# Sheild_Generator_-_Main_unit.net
KiCad netlist of a schematic drawn in EAGLE
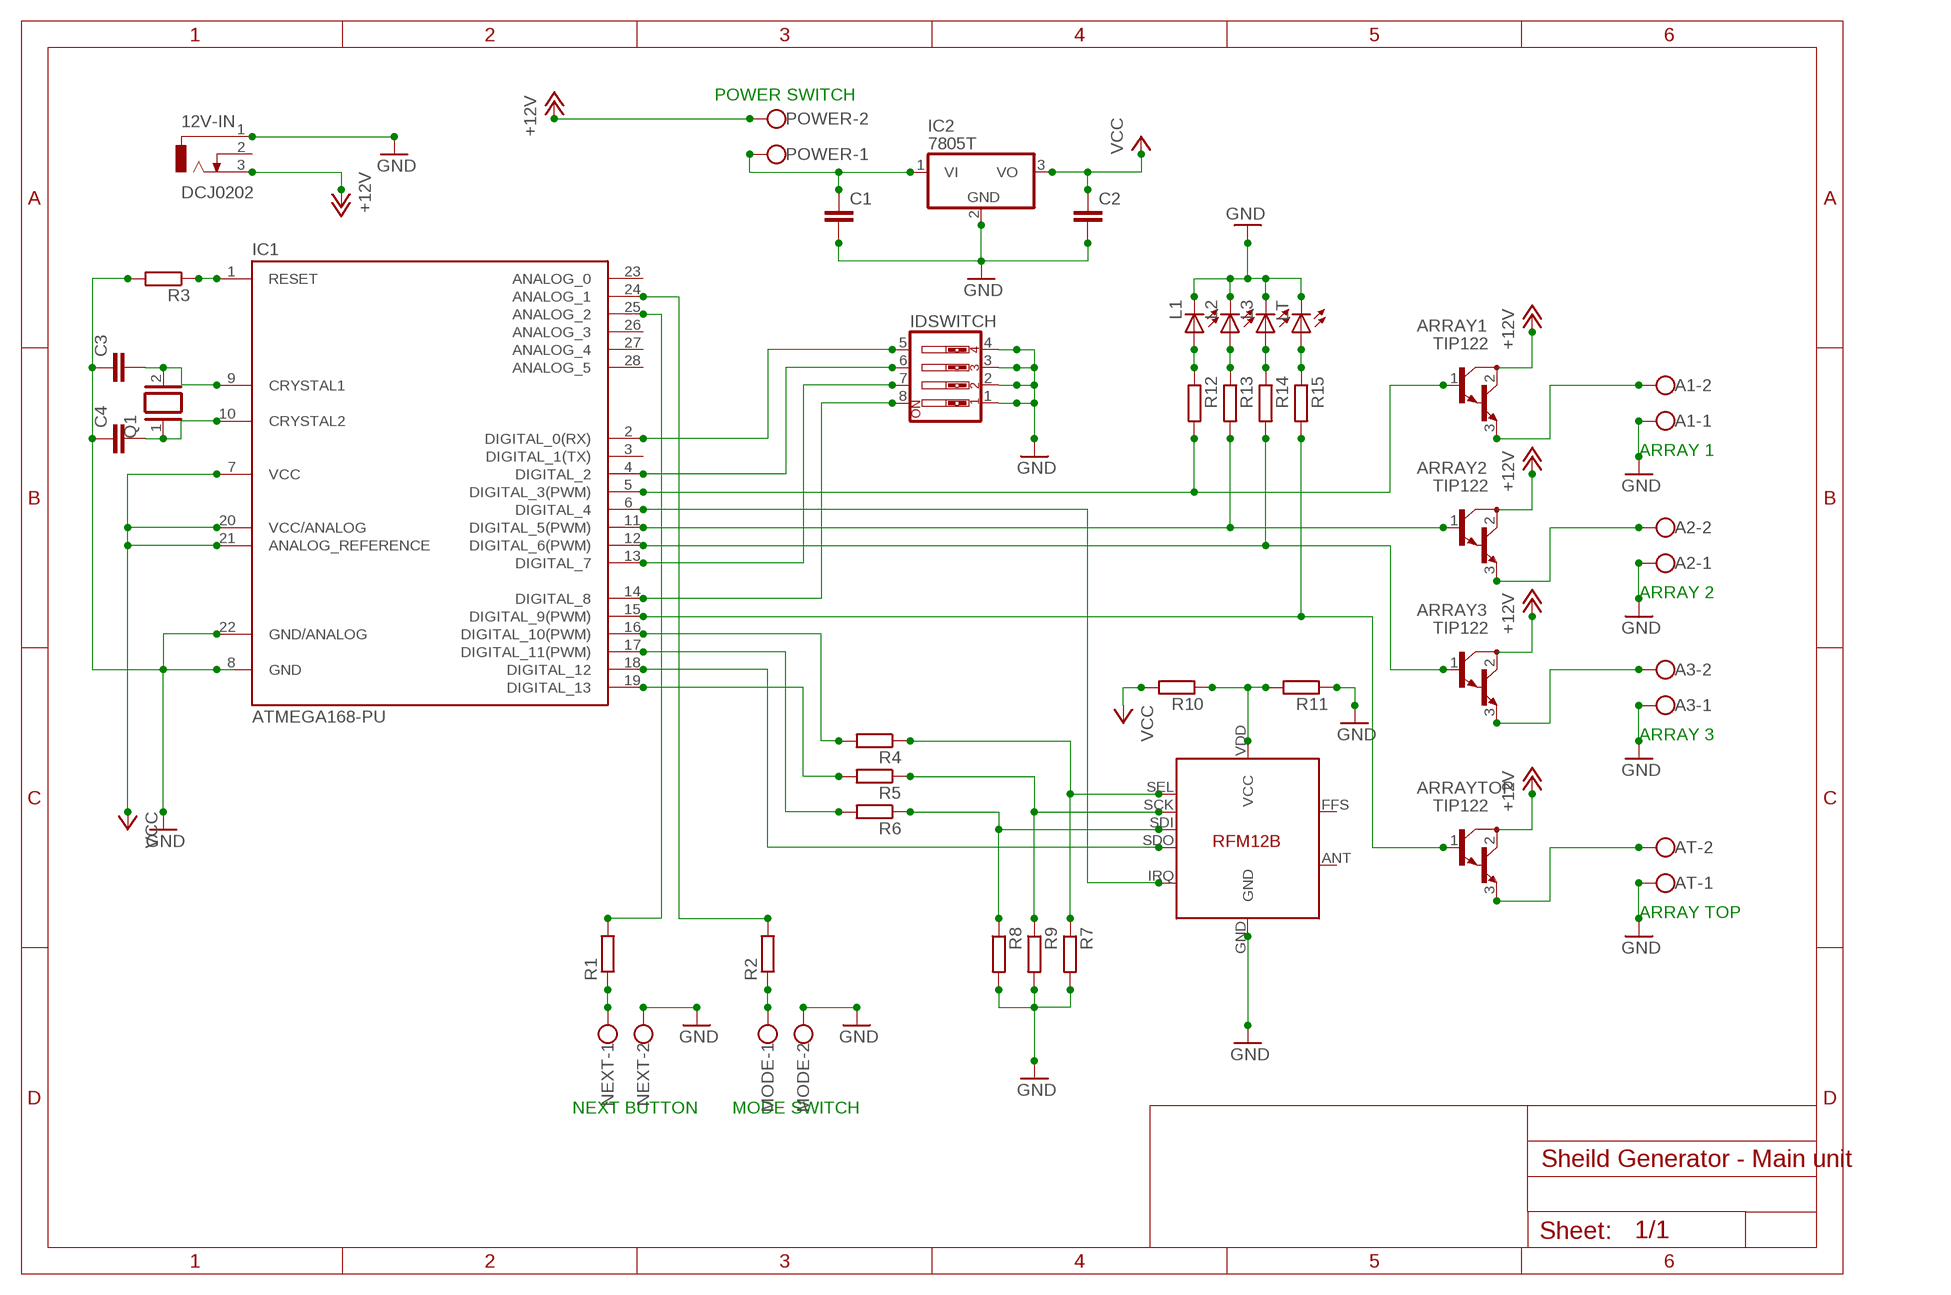
[diagram p0: schematic, sheet 1]

(export (version "E")
  (design (tool "Eeschema 10.0.6"))
  (components
    (comp (ref "12V-IN")
      (value "DCJ0202")
      (footprint "eagle-import:DCJ0202")
      (libsource (lib "eagle-import") (part "DCJ0202"))
    )
    (comp (ref "A1")
      (value "W237-102")
      (footprint "eagle-import:W237-102")
      (fields (field (name "MPN") "237-102"))
      (libsource (lib "eagle-import") (part "W237-102"))
    )
    (comp (ref "A2")
      (value "W237-102")
      (footprint "eagle-import:W237-102")
      (fields (field (name "MPN") "237-102"))
      (libsource (lib "eagle-import") (part "W237-102"))
    )
    (comp (ref "A3")
      (value "W237-102")
      (footprint "eagle-import:W237-102")
      (fields (field (name "MPN") "237-102"))
      (libsource (lib "eagle-import") (part "W237-102"))
    )
    (comp (ref "ARRAY1")
      (value "TIP122")
      (footprint "eagle-import:TO220")
      (libsource (lib "eagle-import") (part "TIP122"))
    )
    (comp (ref "ARRAY2")
      (value "TIP122")
      (footprint "eagle-import:TO220")
      (libsource (lib "eagle-import") (part "TIP122"))
    )
    (comp (ref "ARRAY3")
      (value "TIP122")
      (footprint "eagle-import:TO220")
      (libsource (lib "eagle-import") (part "TIP122"))
    )
    (comp (ref "ARRAYTOP")
      (value "TIP122")
      (footprint "eagle-import:TO220")
      (libsource (lib "eagle-import") (part "TIP122"))
    )
    (comp (ref "AT")
      (value "W237-102")
      (footprint "eagle-import:W237-102")
      (fields (field (name "MPN") "237-102"))
      (libsource (lib "eagle-import") (part "W237-102"))
    )
    (comp (ref "C1")
      (value "C-EU025-024X044")
      (footprint "eagle-import:C025-024X044")
      (libsource (lib "eagle-import") (part "C-EU025-024X044"))
    )
    (comp (ref "C2")
      (value "C-EU025-024X044")
      (footprint "eagle-import:C025-024X044")
      (libsource (lib "eagle-import") (part "C-EU025-024X044"))
    )
    (comp (ref "C3")
      (value "C-EU025-024X044")
      (footprint "eagle-import:C025-024X044")
      (libsource (lib "eagle-import") (part "C-EU025-024X044"))
    )
    (comp (ref "C4")
      (value "C-EU025-024X044")
      (footprint "eagle-import:C025-024X044")
      (libsource (lib "eagle-import") (part "C-EU025-024X044"))
    )
    (comp (ref "IC1")
      (value "ATMEGA168-PU")
      (footprint "eagle-import:DIL28-3")
      (libsource (lib "eagle-import") (part "ATMEGA168-PU"))
    )
    (comp (ref "IC2")
      (value "7805T")
      (footprint "eagle-import:TO220H")
      (libsource (lib "eagle-import") (part "78T05"))
    )
    (comp (ref "IDSWITCH")
      (value "SW_DIP-4")
      (footprint "eagle-import:EDG-04")
      (libsource (lib "eagle-import") (part "SW_DIP-4"))
    )
    (comp (ref "L1")
      (value "LED3MM")
      (footprint "eagle-import:LED3MM")
      (libsource (lib "eagle-import") (part "LED3MM"))
    )
    (comp (ref "L2")
      (value "LED3MM")
      (footprint "eagle-import:LED3MM")
      (libsource (lib "eagle-import") (part "LED3MM"))
    )
    (comp (ref "L3")
      (value "LED3MM")
      (footprint "eagle-import:LED3MM")
      (libsource (lib "eagle-import") (part "LED3MM"))
    )
    (comp (ref "LT")
      (value "LED3MM")
      (footprint "eagle-import:LED3MM")
      (libsource (lib "eagle-import") (part "LED3MM"))
    )
    (comp (ref "MODE")
      (value "W237-102")
      (footprint "eagle-import:W237-102")
      (fields (field (name "MPN") "237-102"))
      (libsource (lib "eagle-import") (part "W237-102"))
    )
    (comp (ref "NEXT")
      (value "W237-102")
      (footprint "eagle-import:W237-102")
      (fields (field (name "MPN") "237-102"))
      (libsource (lib "eagle-import") (part "W237-102"))
    )
    (comp (ref "POWER")
      (value "W237-102")
      (footprint "eagle-import:W237-102")
      (fields (field (name "MPN") "237-102"))
      (libsource (lib "eagle-import") (part "W237-102"))
    )
    (comp (ref "Q1")
      (value "XTAL/S")
      (footprint "eagle-import:QS")
      (libsource (lib "eagle-import") (part "XTAL/S"))
    )
    (comp (ref "R1")
      (value "R-EU_0204/7")
      (footprint "eagle-import:0204_7")
      (libsource (lib "eagle-import") (part "R-EU_0204/7"))
    )
    (comp (ref "R2")
      (value "R-EU_0204/7")
      (footprint "eagle-import:0204_7")
      (libsource (lib "eagle-import") (part "R-EU_0204/7"))
    )
    (comp (ref "R3")
      (value "R-EU_0204/7")
      (footprint "eagle-import:0204_7")
      (libsource (lib "eagle-import") (part "R-EU_0204/7"))
    )
    (comp (ref "R4")
      (value "R-EU_0204/7")
      (footprint "eagle-import:0204_7")
      (libsource (lib "eagle-import") (part "R-EU_0204/7"))
    )
    (comp (ref "R5")
      (value "R-EU_0204/7")
      (footprint "eagle-import:0204_7")
      (libsource (lib "eagle-import") (part "R-EU_0204/7"))
    )
    (comp (ref "R6")
      (value "R-EU_0204/7")
      (footprint "eagle-import:0204_7")
      (libsource (lib "eagle-import") (part "R-EU_0204/7"))
    )
    (comp (ref "R7")
      (value "R-EU_0204/7")
      (footprint "eagle-import:0204_7")
      (libsource (lib "eagle-import") (part "R-EU_0204/7"))
    )
    (comp (ref "R8")
      (value "R-EU_0204/7")
      (footprint "eagle-import:0204_7")
      (libsource (lib "eagle-import") (part "R-EU_0204/7"))
    )
    (comp (ref "R9")
      (value "R-EU_0204/7")
      (footprint "eagle-import:0204_7")
      (libsource (lib "eagle-import") (part "R-EU_0204/7"))
    )
    (comp (ref "R10")
      (value "R-EU_0204/7")
      (footprint "eagle-import:0204_7")
      (libsource (lib "eagle-import") (part "R-EU_0204/7"))
    )
    (comp (ref "R11")
      (value "R-EU_0204/7")
      (footprint "eagle-import:0204_7")
      (libsource (lib "eagle-import") (part "R-EU_0204/7"))
    )
    (comp (ref "R12")
      (value "R-EU_0204/7")
      (footprint "eagle-import:0204_7")
      (libsource (lib "eagle-import") (part "R-EU_0204/7"))
    )
    (comp (ref "R13")
      (value "R-EU_0204/7")
      (footprint "eagle-import:0204_7")
      (libsource (lib "eagle-import") (part "R-EU_0204/7"))
    )
    (comp (ref "R14")
      (value "R-EU_0204/7")
      (footprint "eagle-import:0204_7")
      (libsource (lib "eagle-import") (part "R-EU_0204/7"))
    )
    (comp (ref "R15")
      (value "R-EU_0204/7")
      (footprint "eagle-import:0204_7")
      (libsource (lib "eagle-import") (part "R-EU_0204/7"))
    )
    (comp (ref "U$1")
      (value "RFM12B")
      (footprint "eagle-import:RFM12B")
      (libsource (lib "eagle-import") (part "RFM12B"))
    )
  )
  (nets
    (net (code "1") (name "+12V") (class "Default")
      (node (ref "12V-IN") (pin "3") (pinfunction "3_3") (pintype "passive"))
      (node (ref "ARRAY1") (pin "2") (pinfunction "C_2") (pintype "passive"))
      (node (ref "ARRAY2") (pin "2") (pinfunction "C_2") (pintype "passive"))
      (node (ref "ARRAY3") (pin "2") (pinfunction "C_2") (pintype "passive"))
      (node (ref "ARRAYTOP") (pin "2") (pinfunction "C_2") (pintype "passive"))
      (node (ref "POWER") (pin "2") (pinfunction "KL_2") (pintype "passive"))
    )
    (net (code "2") (name "GND") (class "Default")
      (node (ref "12V-IN") (pin "1") (pinfunction "1_1") (pintype "passive"))
      (node (ref "A1") (pin "1") (pinfunction "KL_1") (pintype "passive"))
      (node (ref "A2") (pin "1") (pinfunction "KL_1") (pintype "passive"))
      (node (ref "A3") (pin "1") (pinfunction "KL_1") (pintype "passive"))
      (node (ref "AT") (pin "1") (pinfunction "KL_1") (pintype "passive"))
      (node (ref "C1") (pin "2") (pinfunction "2_2") (pintype "passive"))
      (node (ref "C2") (pin "2") (pinfunction "2_2") (pintype "passive"))
      (node (ref "C3") (pin "1") (pinfunction "1_1") (pintype "passive"))
      (node (ref "C4") (pin "1") (pinfunction "1_1") (pintype "passive"))
      (node (ref "IC1") (pin "22") (pinfunction "GND/ANALOG_22") (pintype "power_in"))
      (node (ref "IC1") (pin "8") (pinfunction "GND_8") (pintype "power_in"))
      (node (ref "IC2") (pin "2") (pinfunction "GND_2") (pintype "passive"))
      (node (ref "IDSWITCH") (pin "1") (pinfunction "1_1") (pintype "passive"))
      (node (ref "IDSWITCH") (pin "2") (pinfunction "2_2") (pintype "passive"))
      (node (ref "IDSWITCH") (pin "3") (pinfunction "3_3") (pintype "passive"))
      (node (ref "IDSWITCH") (pin "4") (pinfunction "4_4") (pintype "passive"))
      (node (ref "L1") (pin "K") (pinfunction "C_K") (pintype "passive"))
      (node (ref "L2") (pin "K") (pinfunction "C_K") (pintype "passive"))
      (node (ref "L3") (pin "K") (pinfunction "C_K") (pintype "passive"))
      (node (ref "LT") (pin "K") (pinfunction "C_K") (pintype "passive"))
      (node (ref "MODE") (pin "2") (pinfunction "KL_2") (pintype "passive"))
      (node (ref "NEXT") (pin "2") (pinfunction "KL_2") (pintype "passive"))
      (node (ref "R11") (pin "1") (pinfunction "1_1") (pintype "passive"))
      (node (ref "R3") (pin "2") (pinfunction "2_2") (pintype "passive"))
      (node (ref "R7") (pin "2") (pinfunction "2_2") (pintype "passive"))
      (node (ref "R8") (pin "2") (pinfunction "2_2") (pintype "passive"))
      (node (ref "R9") (pin "2") (pinfunction "2_2") (pintype "passive"))
      (node (ref "U$1") (pin "GND") (pinfunction "GND_GND") (pintype "power_in"))
    )
    (net (code "3") (name "Net-(A1B-KL)") (class "Default")
      (node (ref "A1") (pin "2") (pinfunction "KL_2") (pintype "passive"))
      (node (ref "ARRAY1") (pin "3") (pinfunction "E_3") (pintype "passive"))
    )
    (net (code "4") (name "Net-(A2B-KL)") (class "Default")
      (node (ref "A2") (pin "2") (pinfunction "KL_2") (pintype "passive"))
      (node (ref "ARRAY2") (pin "3") (pinfunction "E_3") (pintype "passive"))
    )
    (net (code "5") (name "Net-(A3B-KL)") (class "Default")
      (node (ref "A3") (pin "2") (pinfunction "KL_2") (pintype "passive"))
      (node (ref "ARRAY3") (pin "3") (pinfunction "E_3") (pintype "passive"))
    )
    (net (code "6") (name "Net-(ARRAY1-B)") (class "Default")
      (node (ref "ARRAY1") (pin "1") (pinfunction "B_1") (pintype "passive"))
      (node (ref "IC1") (pin "5") (pinfunction "DIGITAL_3(PWM)_5") (pintype "bidirectional"))
      (node (ref "R12") (pin "2") (pinfunction "2_2") (pintype "passive"))
    )
    (net (code "7") (name "Net-(ARRAY2-B)") (class "Default")
      (node (ref "ARRAY2") (pin "1") (pinfunction "B_1") (pintype "passive"))
      (node (ref "IC1") (pin "11") (pinfunction "DIGITAL_5(PWM)_11") (pintype "bidirectional"))
      (node (ref "R13") (pin "2") (pinfunction "2_2") (pintype "passive"))
    )
    (net (code "8") (name "Net-(ARRAY3-B)") (class "Default")
      (node (ref "ARRAY3") (pin "1") (pinfunction "B_1") (pintype "passive"))
      (node (ref "IC1") (pin "12") (pinfunction "DIGITAL_6(PWM)_12") (pintype "bidirectional"))
      (node (ref "R14") (pin "2") (pinfunction "2_2") (pintype "passive"))
    )
    (net (code "9") (name "Net-(ARRAYTOP-B)") (class "Default")
      (node (ref "ARRAYTOP") (pin "1") (pinfunction "B_1") (pintype "passive"))
      (node (ref "IC1") (pin "15") (pinfunction "DIGITAL_9(PWM)_15") (pintype "bidirectional"))
      (node (ref "R15") (pin "2") (pinfunction "2_2") (pintype "passive"))
    )
    (net (code "10") (name "Net-(ARRAYTOP-E)") (class "Default")
      (node (ref "ARRAYTOP") (pin "3") (pinfunction "E_3") (pintype "passive"))
      (node (ref "AT") (pin "2") (pinfunction "KL_2") (pintype "passive"))
    )
    (net (code "11") (name "Net-(IC1-ANALOG_1)") (class "Default")
      (node (ref "IC1") (pin "24") (pinfunction "ANALOG_1_24") (pintype "bidirectional"))
      (node (ref "R2") (pin "2") (pinfunction "2_2") (pintype "passive"))
    )
    (net (code "12") (name "Net-(IC1-ANALOG_2)") (class "Default")
      (node (ref "IC1") (pin "25") (pinfunction "ANALOG_2_25") (pintype "bidirectional"))
      (node (ref "R1") (pin "2") (pinfunction "2_2") (pintype "passive"))
    )
    (net (code "13") (name "Net-(IC1-CRYSTAL1)") (class "Default")
      (node (ref "C3") (pin "2") (pinfunction "2_2") (pintype "passive"))
      (node (ref "IC1") (pin "9") (pinfunction "CRYSTAL1_9") (pintype "bidirectional"))
      (node (ref "Q1") (pin "2") (pinfunction "2_2") (pintype "passive"))
    )
    (net (code "14") (name "Net-(IC1-CRYSTAL2)") (class "Default")
      (node (ref "C4") (pin "2") (pinfunction "2_2") (pintype "passive"))
      (node (ref "IC1") (pin "10") (pinfunction "CRYSTAL2_10") (pintype "bidirectional"))
      (node (ref "Q1") (pin "1") (pinfunction "1_1") (pintype "passive"))
    )
    (net (code "15") (name "Net-(IC1-DIGITAL_0(RX))") (class "Default")
      (node (ref "IC1") (pin "2") (pinfunction "DIGITAL_0(RX)_2") (pintype "bidirectional"))
      (node (ref "IDSWITCH") (pin "5") (pinfunction "5_5") (pintype "passive"))
    )
    (net (code "16") (name "Net-(IC1-DIGITAL_2)") (class "Default")
      (node (ref "IC1") (pin "4") (pinfunction "DIGITAL_2_4") (pintype "bidirectional"))
      (node (ref "IDSWITCH") (pin "6") (pinfunction "6_6") (pintype "passive"))
    )
    (net (code "17") (name "Net-(IC1-DIGITAL_4)") (class "Default")
      (node (ref "IC1") (pin "6") (pinfunction "DIGITAL_4_6") (pintype "bidirectional"))
      (node (ref "U$1") (pin "IRQ") (pinfunction "IRQ_IRQ") (pintype "open_collector"))
    )
    (net (code "18") (name "Net-(IC1-DIGITAL_7)") (class "Default")
      (node (ref "IC1") (pin "13") (pinfunction "DIGITAL_7_13") (pintype "bidirectional"))
      (node (ref "IDSWITCH") (pin "7") (pinfunction "7_7") (pintype "passive"))
    )
    (net (code "19") (name "Net-(IC1-DIGITAL_8)") (class "Default")
      (node (ref "IC1") (pin "14") (pinfunction "DIGITAL_8_14") (pintype "bidirectional"))
      (node (ref "IDSWITCH") (pin "8") (pinfunction "8_8") (pintype "passive"))
    )
    (net (code "20") (name "Net-(IC1-DIGITAL_10(PWM))") (class "Default")
      (node (ref "IC1") (pin "16") (pinfunction "DIGITAL_10(PWM)_16") (pintype "bidirectional"))
      (node (ref "R4") (pin "2") (pinfunction "2_2") (pintype "passive"))
    )
    (net (code "21") (name "Net-(IC1-DIGITAL_11(PWM))") (class "Default")
      (node (ref "IC1") (pin "17") (pinfunction "DIGITAL_11(PWM)_17") (pintype "bidirectional"))
      (node (ref "R6") (pin "2") (pinfunction "2_2") (pintype "passive"))
    )
    (net (code "22") (name "Net-(IC1-DIGITAL_12)") (class "Default")
      (node (ref "IC1") (pin "18") (pinfunction "DIGITAL_12_18") (pintype "bidirectional"))
      (node (ref "U$1") (pin "SDO") (pinfunction "SDO_SDO") (pintype "output"))
    )
    (net (code "23") (name "Net-(IC1-DIGITAL_13)") (class "Default")
      (node (ref "IC1") (pin "19") (pinfunction "DIGITAL_13_19") (pintype "bidirectional"))
      (node (ref "R5") (pin "2") (pinfunction "2_2") (pintype "passive"))
    )
    (net (code "24") (name "Net-(IC1-RESET)") (class "Default")
      (node (ref "IC1") (pin "1") (pinfunction "RESET_1") (pintype "bidirectional"))
      (node (ref "R3") (pin "1") (pinfunction "1_1") (pintype "passive"))
    )
    (net (code "25") (name "Net-(IC2-VI)") (class "Default")
      (node (ref "C1") (pin "1") (pinfunction "1_1") (pintype "passive"))
      (node (ref "IC2") (pin "1") (pinfunction "VI_1") (pintype "input"))
      (node (ref "POWER") (pin "1") (pinfunction "KL_1") (pintype "passive"))
    )
    (net (code "26") (name "Net-(L1-PadA)") (class "Default")
      (node (ref "L1") (pin "A") (pinfunction "A_A") (pintype "passive"))
      (node (ref "R12") (pin "1") (pinfunction "1_1") (pintype "passive"))
    )
    (net (code "27") (name "Net-(L2-PadA)") (class "Default")
      (node (ref "L2") (pin "A") (pinfunction "A_A") (pintype "passive"))
      (node (ref "R13") (pin "1") (pinfunction "1_1") (pintype "passive"))
    )
    (net (code "28") (name "Net-(L3-PadA)") (class "Default")
      (node (ref "L3") (pin "A") (pinfunction "A_A") (pintype "passive"))
      (node (ref "R14") (pin "1") (pinfunction "1_1") (pintype "passive"))
    )
    (net (code "29") (name "Net-(LT-PadA)") (class "Default")
      (node (ref "LT") (pin "A") (pinfunction "A_A") (pintype "passive"))
      (node (ref "R15") (pin "1") (pinfunction "1_1") (pintype "passive"))
    )
    (net (code "30") (name "Net-(MODEA-KL)") (class "Default")
      (node (ref "MODE") (pin "1") (pinfunction "KL_1") (pintype "passive"))
      (node (ref "R2") (pin "1") (pinfunction "1_1") (pintype "passive"))
    )
    (net (code "31") (name "Net-(NEXTA-KL)") (class "Default")
      (node (ref "NEXT") (pin "1") (pinfunction "KL_1") (pintype "passive"))
      (node (ref "R1") (pin "1") (pinfunction "1_1") (pintype "passive"))
    )
    (net (code "32") (name "Net-(R4-Pad1)") (class "Default")
      (node (ref "R4") (pin "1") (pinfunction "1_1") (pintype "passive"))
      (node (ref "R7") (pin "1") (pinfunction "1_1") (pintype "passive"))
      (node (ref "U$1") (pin "SEL") (pinfunction "SEL_SEL") (pintype "input"))
    )
    (net (code "33") (name "Net-(R5-Pad1)") (class "Default")
      (node (ref "R5") (pin "1") (pinfunction "1_1") (pintype "passive"))
      (node (ref "R9") (pin "1") (pinfunction "1_1") (pintype "passive"))
      (node (ref "U$1") (pin "SCK") (pinfunction "SCK_SCK") (pintype "input"))
    )
    (net (code "34") (name "Net-(R6-Pad1)") (class "Default")
      (node (ref "R6") (pin "1") (pinfunction "1_1") (pintype "passive"))
      (node (ref "R8") (pin "1") (pinfunction "1_1") (pintype "passive"))
      (node (ref "U$1") (pin "SDI") (pinfunction "SDI_SDI") (pintype "input"))
    )
    (net (code "35") (name "Net-(U$1-VCC)") (class "Default")
      (node (ref "R10") (pin "1") (pinfunction "1_1") (pintype "passive"))
      (node (ref "R11") (pin "2") (pinfunction "2_2") (pintype "passive"))
      (node (ref "U$1") (pin "VDD") (pinfunction "VCC_VDD") (pintype "power_in"))
    )
    (net (code "36") (name "VCC") (class "Default")
      (node (ref "C2") (pin "1") (pinfunction "1_1") (pintype "passive"))
      (node (ref "IC1") (pin "20") (pinfunction "VCC/ANALOG_20") (pintype "passive"))
      (node (ref "IC1") (pin "21") (pinfunction "ANALOG_REFERENCE_21") (pintype "passive"))
      (node (ref "IC1") (pin "7") (pinfunction "VCC_7") (pintype "power_in"))
      (node (ref "IC2") (pin "3") (pinfunction "VO_3") (pintype "passive"))
      (node (ref "R10") (pin "2") (pinfunction "2_2") (pintype "passive"))
    )
    (net (code "37") (name "unconnected-(12V-IN-Pad2)") (class "Default")
      (node (ref "12V-IN") (pin "2") (pinfunction "2_2") (pintype "passive"))
    )
    (net (code "38") (name "unconnected-(IC1-ANALOG_0-Pad23)") (class "Default")
      (node (ref "IC1") (pin "23") (pinfunction "ANALOG_0_23") (pintype "bidirectional"))
    )
    (net (code "39") (name "unconnected-(IC1-ANALOG_3-Pad26)") (class "Default")
      (node (ref "IC1") (pin "26") (pinfunction "ANALOG_3_26") (pintype "bidirectional"))
    )
    (net (code "40") (name "unconnected-(IC1-ANALOG_4-Pad27)") (class "Default")
      (node (ref "IC1") (pin "27") (pinfunction "ANALOG_4_27") (pintype "bidirectional"))
    )
    (net (code "41") (name "unconnected-(IC1-ANALOG_5-Pad28)") (class "Default")
      (node (ref "IC1") (pin "28") (pinfunction "ANALOG_5_28") (pintype "bidirectional"))
    )
    (net (code "42") (name "unconnected-(IC1-DIGITAL_1(TX)-Pad3)") (class "Default")
      (node (ref "IC1") (pin "3") (pinfunction "DIGITAL_1(TX)_3") (pintype "bidirectional"))
    )
    (net (code "43") (name "unconnected-(U$1-PadANT)") (class "Default")
      (node (ref "U$1") (pin "ANT") (pinfunction "ANT_ANT") (pintype "passive"))
    )
    (net (code "44") (name "unconnected-(U$1-PadFFS)") (class "Default")
      (node (ref "U$1") (pin "FFS") (pinfunction "FFS_FFS") (pintype "bidirectional"))
    )
  )
)
